# balloon_sensor_board.net
KiCad netlist of a schematic drawn in EAGLE
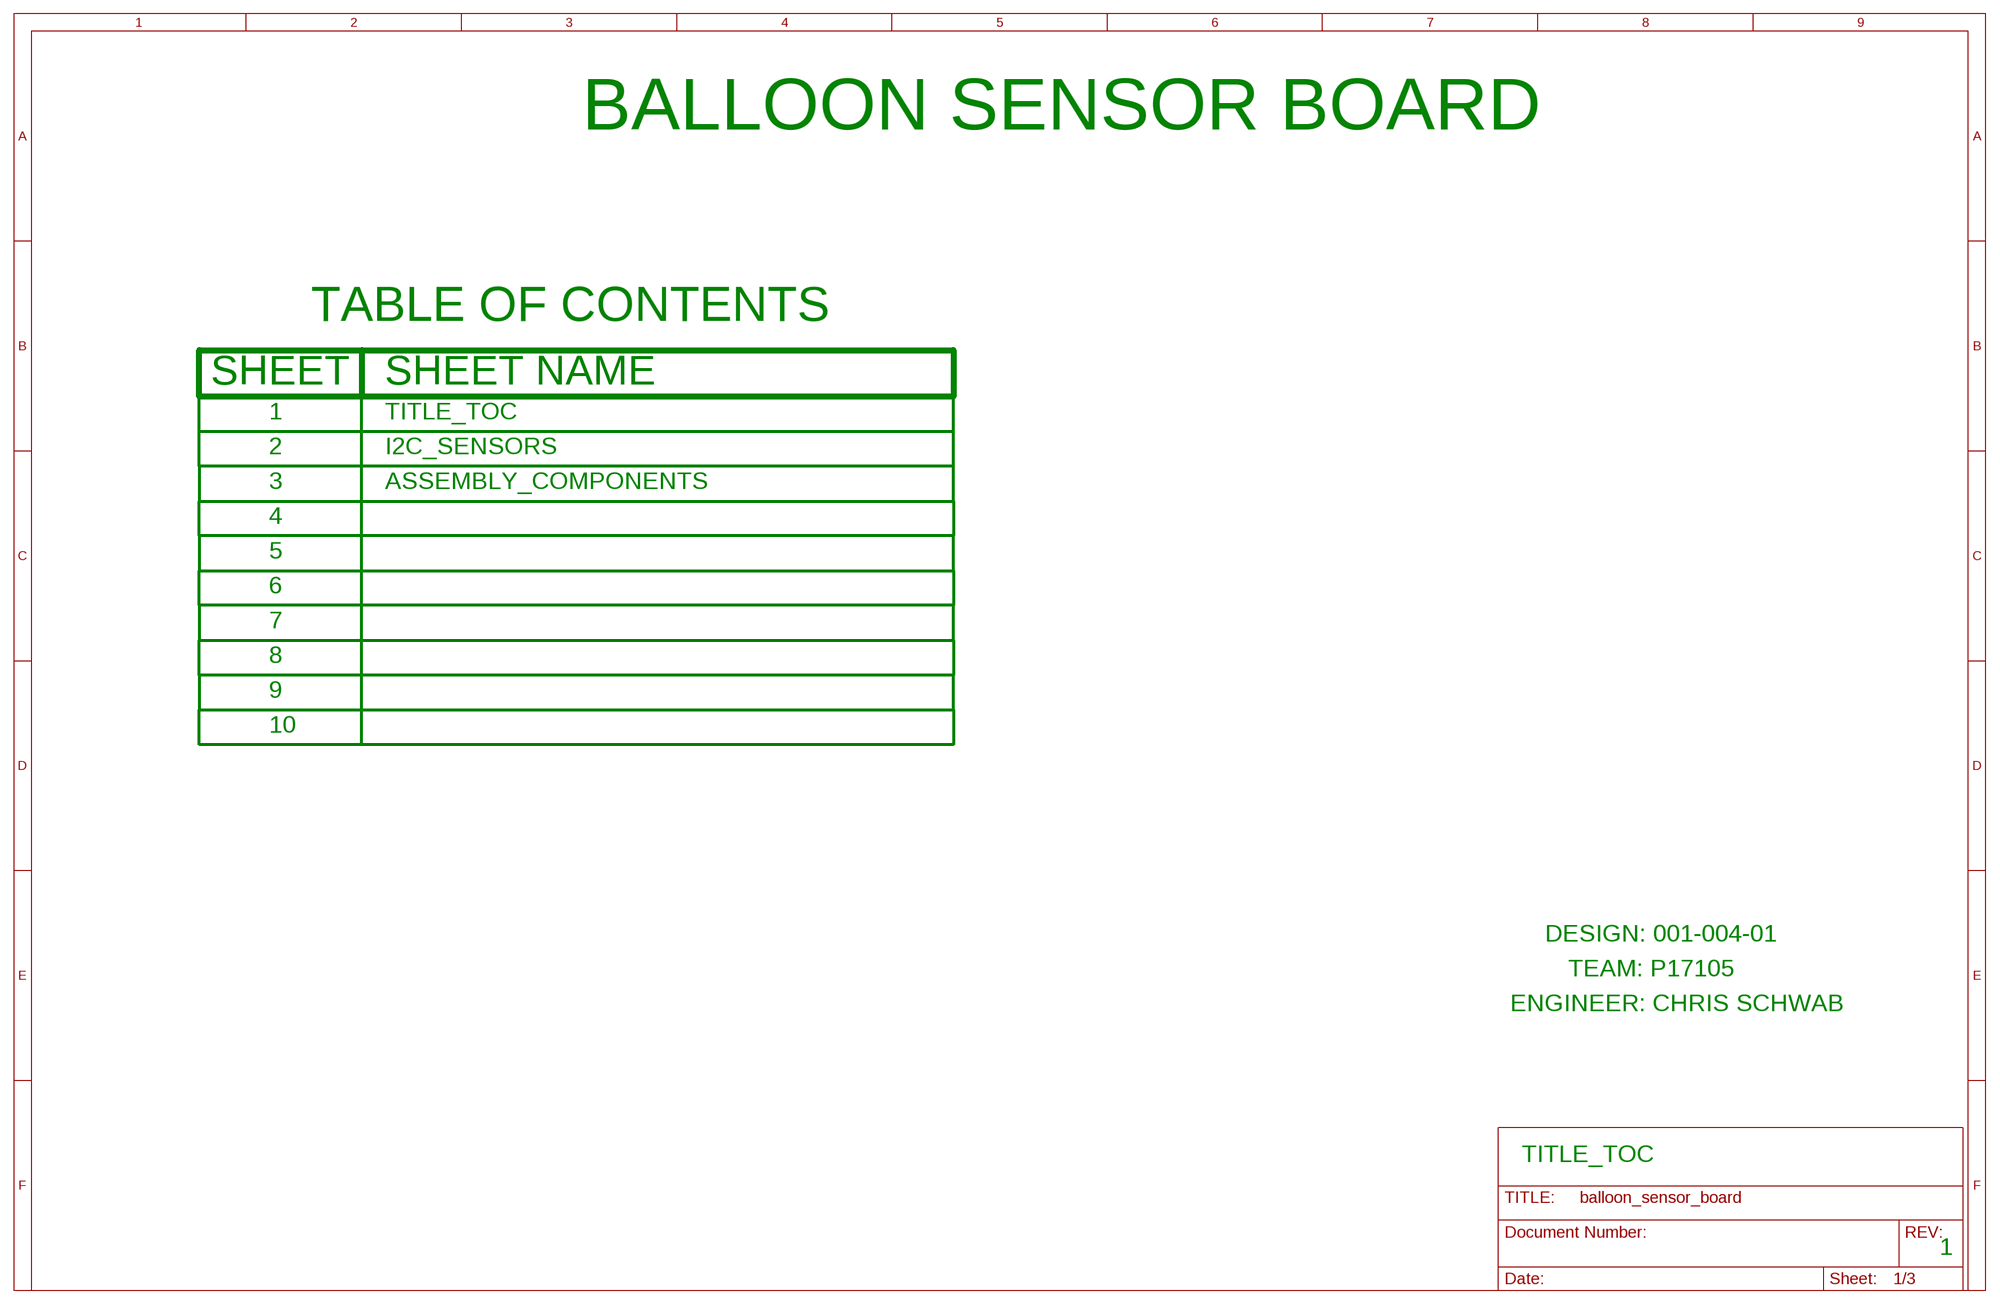
[diagram p0: schematic, sheet 1]
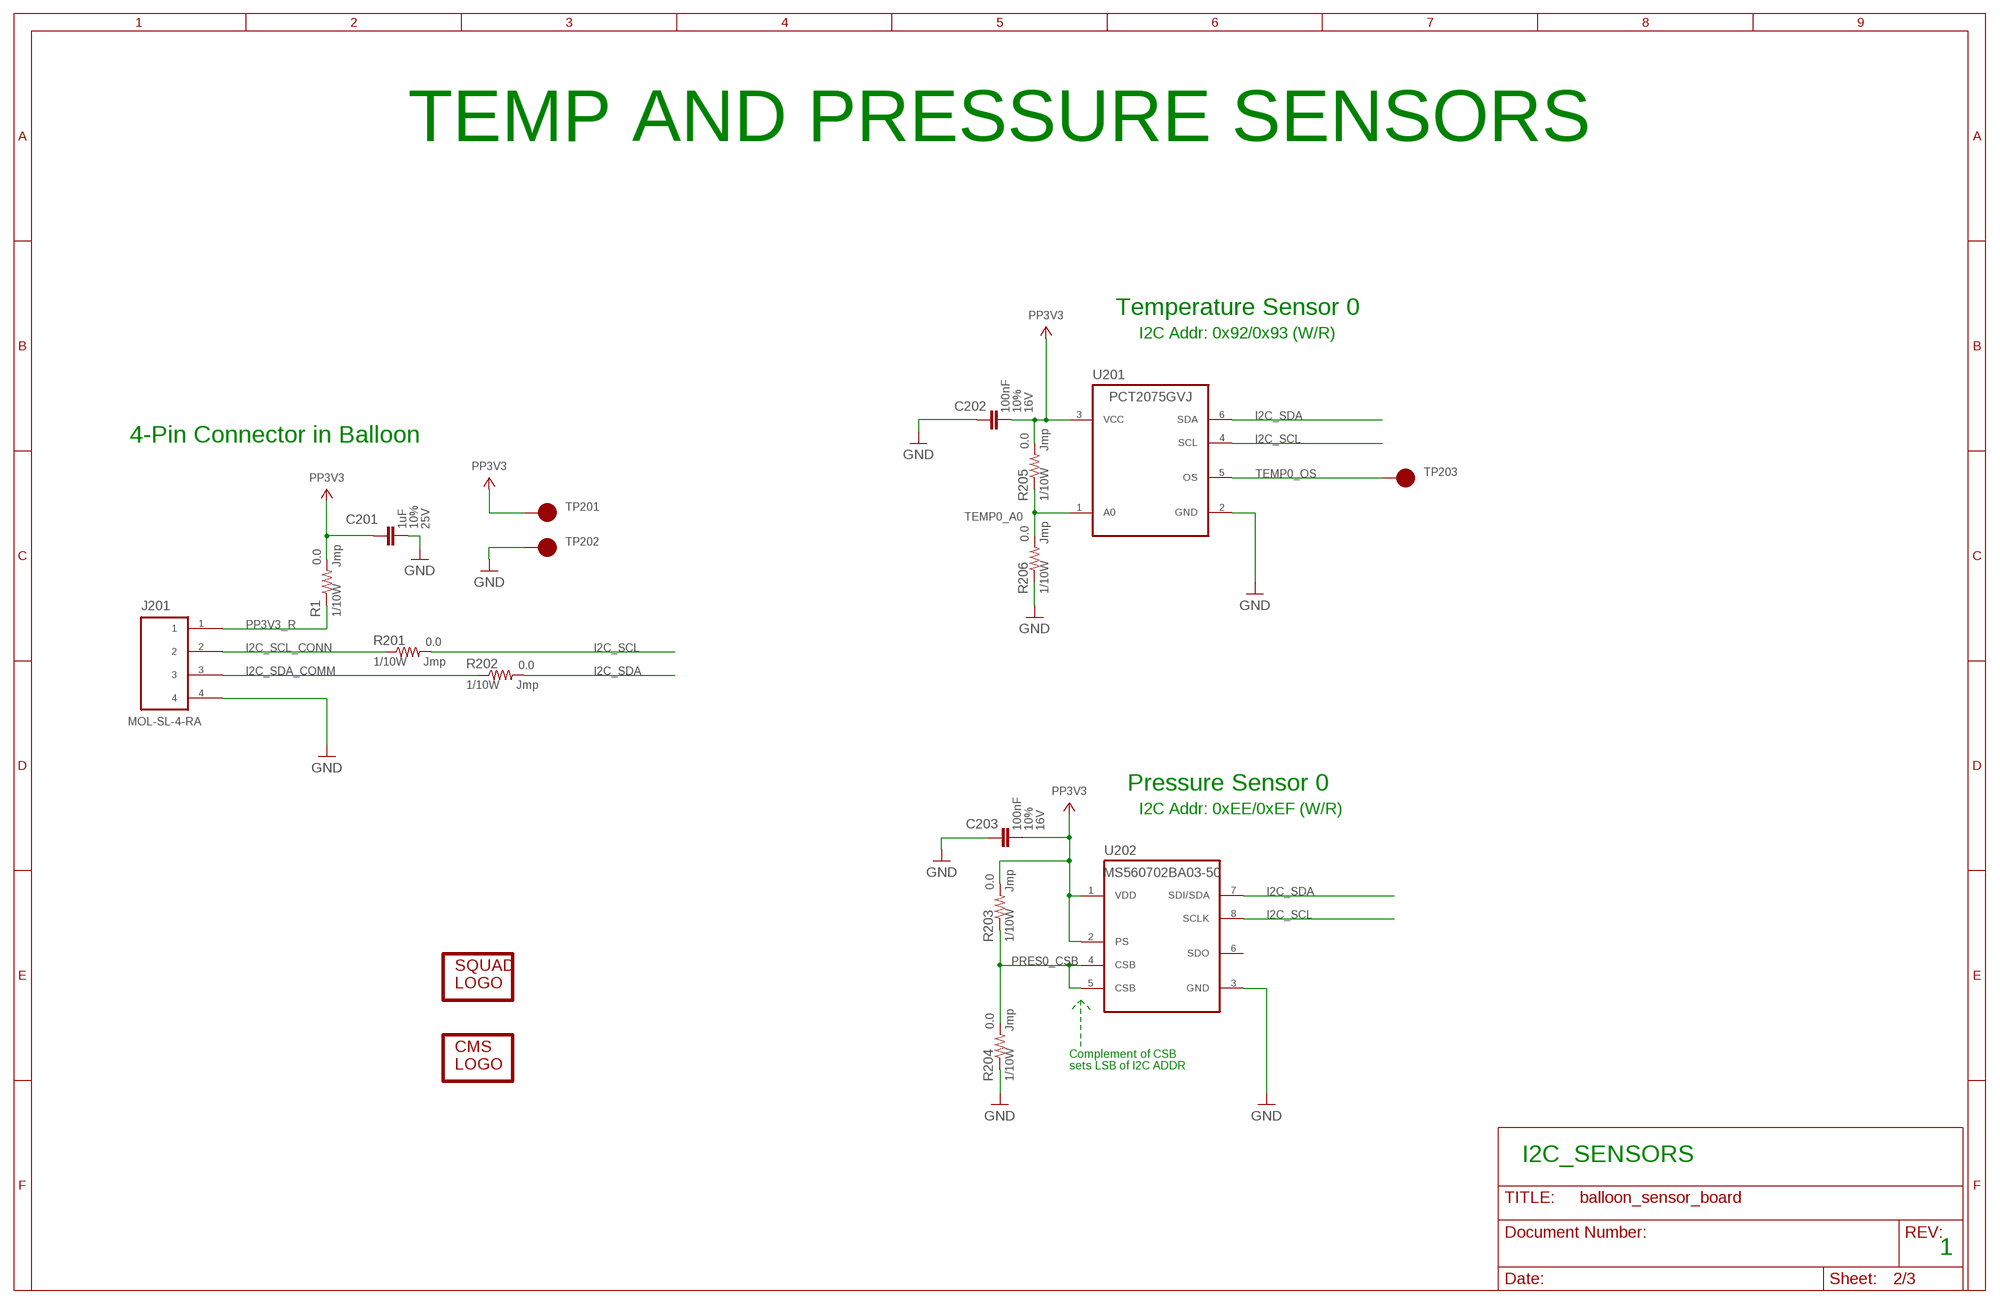
[diagram p1: schematic, sheet 2]
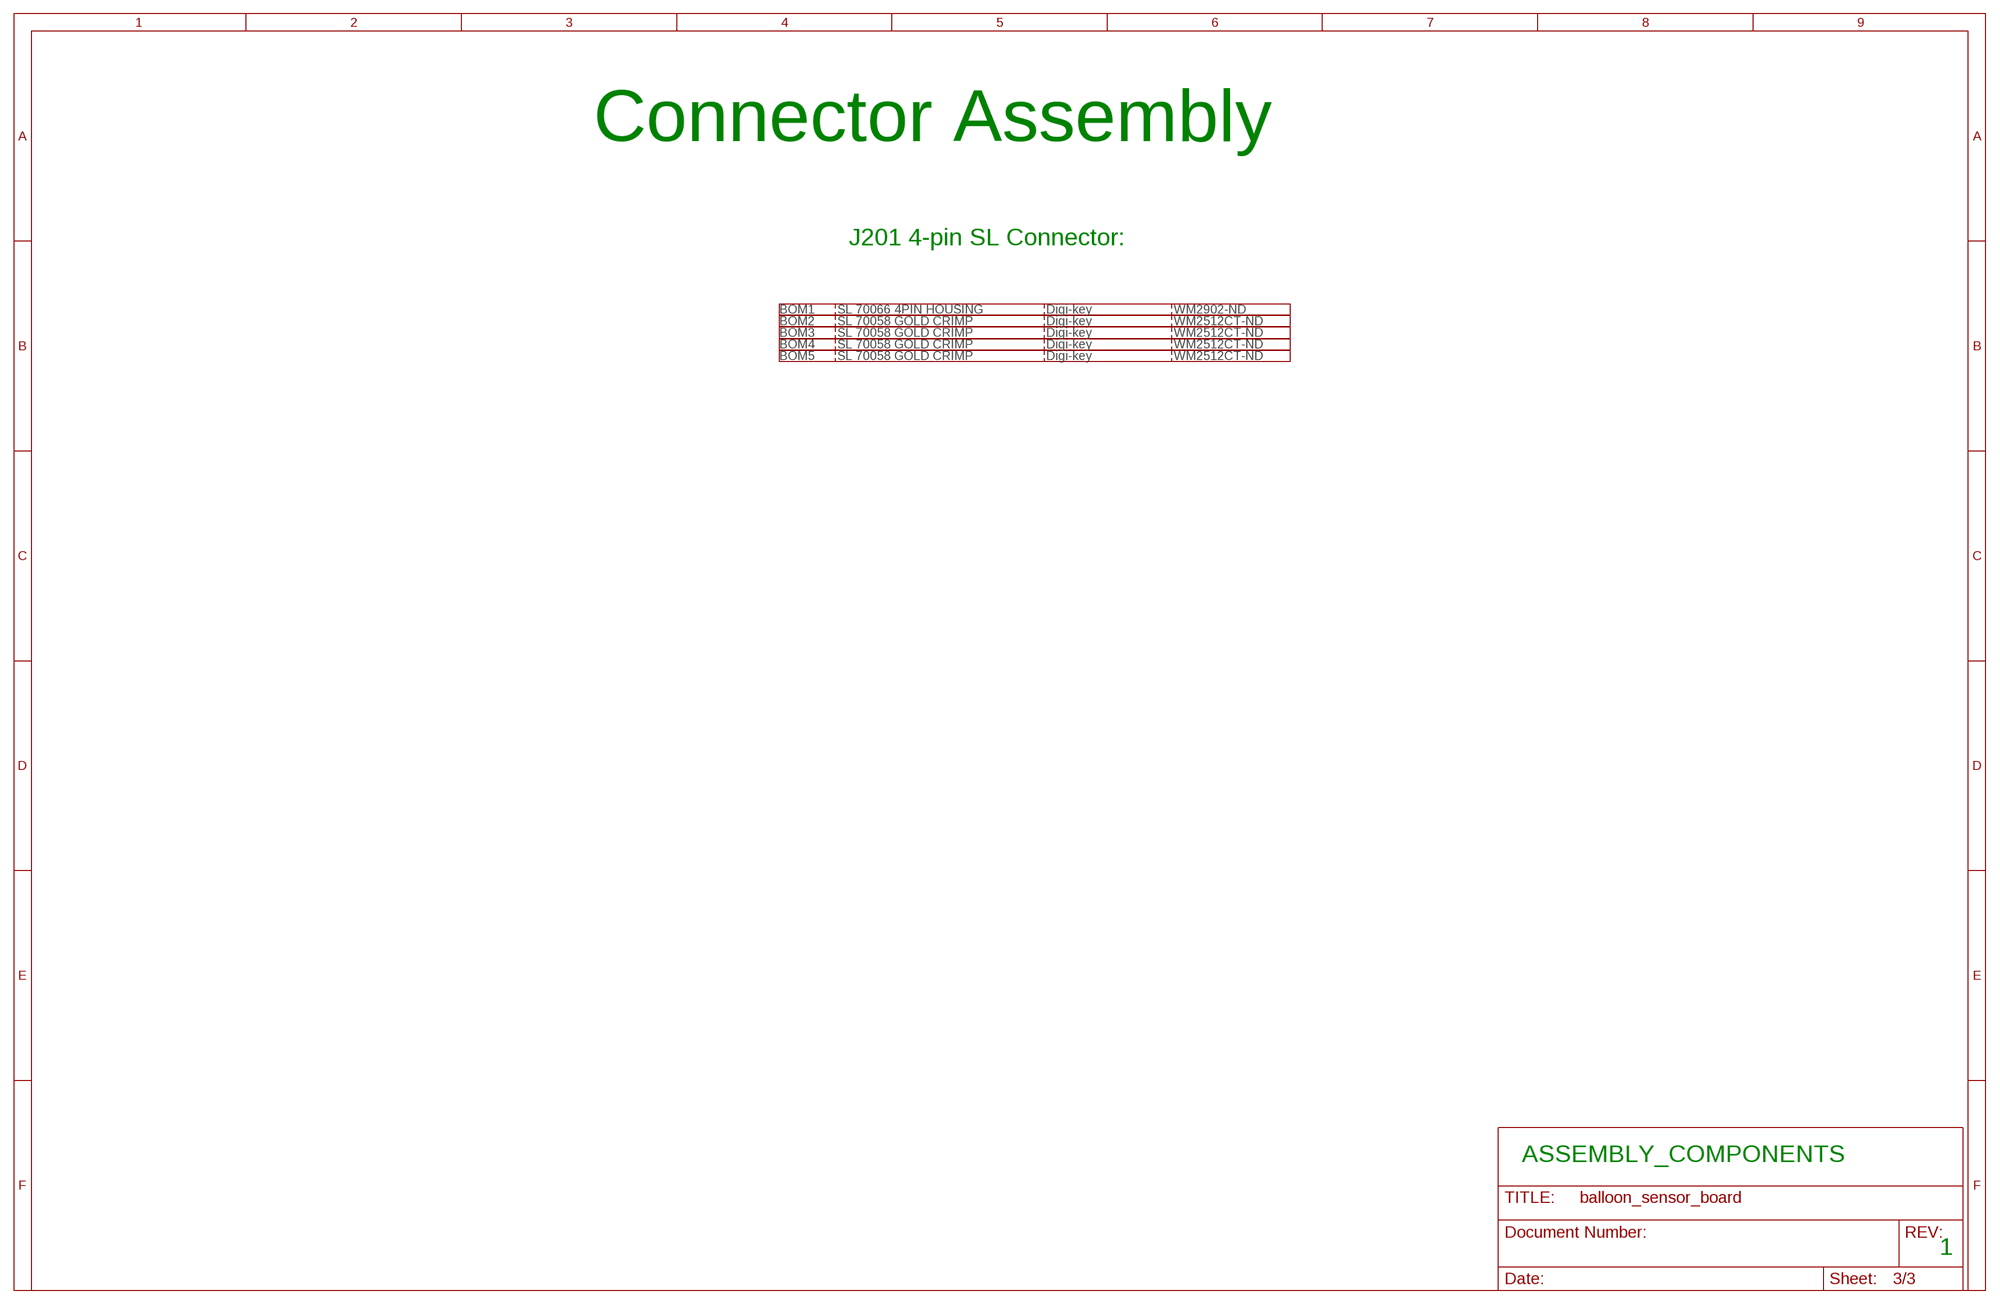
[diagram p2: schematic, sheet 3]

(export (version "E")
  (design (tool "Eeschema 10.0.6"))
  (components
    (comp (ref "BOM1")
      (value "SL 70066 4PIN HOUSING")
      (footprint "eagle-import:BLANK")
      (fields (field (name "MANUFACTURER") "Molex"))
      (libsource (lib "eagle-import") (part "BOM_LINE_ITEM_BLI4"))
    )
    (comp (ref "BOM2")
      (value "SL 70058 GOLD CRIMP")
      (footprint "eagle-import:BLANK")
      (fields (field (name "MANUFACTURER") "Molex"))
      (libsource (lib "eagle-import") (part "BOM_LINE_ITEM_BLI6"))
    )
    (comp (ref "BOM3")
      (value "SL 70058 GOLD CRIMP")
      (footprint "eagle-import:BLANK")
      (fields (field (name "MANUFACTURER") "Molex"))
      (libsource (lib "eagle-import") (part "BOM_LINE_ITEM_BLI6"))
    )
    (comp (ref "BOM4")
      (value "SL 70058 GOLD CRIMP")
      (footprint "eagle-import:BLANK")
      (fields (field (name "MANUFACTURER") "Molex"))
      (libsource (lib "eagle-import") (part "BOM_LINE_ITEM_BLI6"))
    )
    (comp (ref "BOM5")
      (value "SL 70058 GOLD CRIMP")
      (footprint "eagle-import:BLANK")
      (fields (field (name "MANUFACTURER") "Molex"))
      (libsource (lib "eagle-import") (part "BOM_LINE_ITEM_BLI6"))
    )
    (comp (ref "C201")
      (value "1uF")
      (footprint "eagle-import:C0603")
      (fields
        (field (name "MANUFACTURER") "Murata")
        (field (name "TOLERANCE") "10%")
        (field (name "VOLTAGE") "25V")
      )
      (libsource (lib "eagle-import") (part "CAP_0603_1UF0"))
    )
    (comp (ref "C202")
      (value "100nF")
      (footprint "eagle-import:C0603")
      (fields
        (field (name "MANUFACTURER") "Murata")
        (field (name "TOLERANCE") "10%")
        (field (name "VOLTAGE") "16V")
      )
      (libsource (lib "eagle-import") (part "CAP_0603_100NF0"))
    )
    (comp (ref "C203")
      (value "100nF")
      (footprint "eagle-import:C0603")
      (fields
        (field (name "MANUFACTURER") "Murata")
        (field (name "TOLERANCE") "10%")
        (field (name "VOLTAGE") "16V")
      )
      (libsource (lib "eagle-import") (part "CAP_0603_100NF0"))
    )
    (comp (ref "J201")
      (value "MOL-SL-4-RA")
      (footprint "eagle-import:MOLSL-4-RA")
      (fields (field (name "MANUFACTURER") "Molex"))
      (libsource (lib "eagle-import") (part "MOLSL_4PIN_RA_SL4RA"))
    )
    (comp (ref "LOGO201")
      (value "SQUAD_LOGO")
      (footprint "eagle-import:SQUAD_LOGO")
      (libsource (lib "eagle-import") (part "SQUAD_LOGO"))
    )
    (comp (ref "LOGO202")
      (value "CMS_LOGO")
      (footprint "eagle-import:CMS_LOGO")
      (libsource (lib "eagle-import") (part "CMS_LOGO"))
    )
    (comp (ref "R1")
      (value "0.0")
      (footprint "eagle-import:R0603")
      (fields
        (field (name "MANUFACTURER") "Panasonic")
        (field (name "POWER") "1/10W")
        (field (name "TOLERANCE") "Jmp")
      )
      (libsource (lib "eagle-import") (part "RES_0603_0R0"))
    )
    (comp (ref "R201")
      (value "0.0")
      (footprint "eagle-import:R0603")
      (fields
        (field (name "MANUFACTURER") "Panasonic")
        (field (name "POWER") "1/10W")
        (field (name "TOLERANCE") "Jmp")
      )
      (libsource (lib "eagle-import") (part "RES_0603_0R0"))
    )
    (comp (ref "R202")
      (value "0.0")
      (footprint "eagle-import:R0603")
      (fields
        (field (name "MANUFACTURER") "Panasonic")
        (field (name "POWER") "1/10W")
        (field (name "TOLERANCE") "Jmp")
      )
      (libsource (lib "eagle-import") (part "RES_0603_0R0"))
    )
    (comp (ref "R203")
      (value "0.0")
      (footprint "eagle-import:R0603")
      (fields
        (field (name "MANUFACTURER") "Panasonic")
        (field (name "POWER") "1/10W")
        (field (name "TOLERANCE") "Jmp")
      )
      (libsource (lib "eagle-import") (part "RES_0603_0R0"))
    )
    (comp (ref "R204")
      (value "0.0")
      (footprint "eagle-import:R0603")
      (fields
        (field (name "MANUFACTURER") "Panasonic")
        (field (name "POWER") "1/10W")
        (field (name "TOLERANCE") "Jmp")
      )
      (libsource (lib "eagle-import") (part "RES_0603_0R0"))
    )
    (comp (ref "R205")
      (value "0.0")
      (footprint "eagle-import:R0603")
      (fields
        (field (name "MANUFACTURER") "Panasonic")
        (field (name "POWER") "1/10W")
        (field (name "TOLERANCE") "Jmp")
      )
      (libsource (lib "eagle-import") (part "RES_0603_0R0"))
    )
    (comp (ref "R206")
      (value "0.0")
      (footprint "eagle-import:R0603")
      (fields
        (field (name "MANUFACTURER") "Panasonic")
        (field (name "POWER") "1/10W")
        (field (name "TOLERANCE") "Jmp")
      )
      (libsource (lib "eagle-import") (part "RES_0603_0R0"))
    )
    (comp (ref "TP201")
      (value "TEST_POINT_SMT_15R_SMD")
      (footprint "eagle-import:TP15R")
      (libsource (lib "eagle-import") (part "TEST_POINT_SMT_15R_SMD"))
    )
    (comp (ref "TP202")
      (value "TEST_POINT_SMT_15R_SMD")
      (footprint "eagle-import:TP15R")
      (libsource (lib "eagle-import") (part "TEST_POINT_SMT_15R_SMD"))
    )
    (comp (ref "TP203")
      (value "TEST_POINT_SMT_15R_SMD")
      (footprint "eagle-import:TP15R")
      (libsource (lib "eagle-import") (part "TEST_POINT_SMT_15R_SMD"))
    )
    (comp (ref "U201")
      (value "PCT2075GVJ")
      (footprint "eagle-import:TSOP95P080X055-6N")
      (fields (field (name "MANUFACTURER") "NXP"))
      (libsource (lib "eagle-import") (part "PCT2075GV_TSOP6"))
    )
    (comp (ref "U202")
      (value "MS560702BA03-50")
      (footprint "eagle-import:SMD125P110X060-8N")
      (fields (field (name "MANUFACTURER") "TE Connectivity"))
      (libsource (lib "eagle-import") (part "MS5607_8SMD-02BA03"))
    )
  )
  (nets
    (net (code "1") (name "GND") (class "Default")
      (node (ref "C201") (pin "2") (pinfunction "2_2") (pintype "passive"))
      (node (ref "C202") (pin "1") (pinfunction "1_1") (pintype "passive"))
      (node (ref "C203") (pin "1") (pinfunction "1_1") (pintype "passive"))
      (node (ref "J201") (pin "4") (pinfunction "4_4") (pintype "bidirectional"))
      (node (ref "R204") (pin "1") (pinfunction "1_1") (pintype "passive"))
      (node (ref "R206") (pin "1") (pinfunction "1_1") (pintype "passive"))
      (node (ref "TP202") (pin "TP") (pinfunction "TP_TP") (pintype "passive"))
      (node (ref "U201") (pin "2") (pinfunction "GND_2") (pintype "power_in"))
      (node (ref "U202") (pin "3") (pinfunction "GND_3") (pintype "power_in"))
    )
    (net (code "2") (name "I2C_SCL") (class "Default")
      (node (ref "R201") (pin "2") (pinfunction "2_2") (pintype "passive"))
      (node (ref "U201") (pin "4") (pinfunction "SCL_4") (pintype "input"))
      (node (ref "U202") (pin "8") (pinfunction "SCLK_8") (pintype "input"))
    )
    (net (code "3") (name "I2C_SCL_CONN") (class "Default")
      (node (ref "J201") (pin "2") (pinfunction "2_2") (pintype "bidirectional"))
      (node (ref "R201") (pin "1") (pinfunction "1_1") (pintype "passive"))
    )
    (net (code "4") (name "I2C_SDA") (class "Default")
      (node (ref "R202") (pin "2") (pinfunction "2_2") (pintype "passive"))
      (node (ref "U201") (pin "6") (pinfunction "SDA_6") (pintype "bidirectional"))
      (node (ref "U202") (pin "7") (pinfunction "SDI/SDA_7") (pintype "bidirectional"))
    )
    (net (code "5") (name "I2C_SDA_COMM") (class "Default")
      (node (ref "J201") (pin "3") (pinfunction "3_3") (pintype "bidirectional"))
      (node (ref "R202") (pin "1") (pinfunction "1_1") (pintype "passive"))
    )
    (net (code "6") (name "PP3V3") (class "Default")
      (node (ref "C201") (pin "1") (pinfunction "1_1") (pintype "passive"))
      (node (ref "C202") (pin "2") (pinfunction "2_2") (pintype "passive"))
      (node (ref "C203") (pin "2") (pinfunction "2_2") (pintype "passive"))
      (node (ref "R1") (pin "2") (pinfunction "2_2") (pintype "passive"))
      (node (ref "R203") (pin "2") (pinfunction "2_2") (pintype "passive"))
      (node (ref "R205") (pin "2") (pinfunction "2_2") (pintype "passive"))
      (node (ref "TP201") (pin "TP") (pinfunction "TP_TP") (pintype "passive"))
      (node (ref "U201") (pin "3") (pinfunction "VCC_3") (pintype "power_in"))
      (node (ref "U202") (pin "1") (pinfunction "VDD_1") (pintype "power_in"))
      (node (ref "U202") (pin "2") (pinfunction "PS_2") (pintype "input"))
    )
    (net (code "7") (name "PP3V3_R") (class "Default")
      (node (ref "J201") (pin "1") (pinfunction "1_1") (pintype "bidirectional"))
      (node (ref "R1") (pin "1") (pinfunction "1_1") (pintype "passive"))
    )
    (net (code "8") (name "PRES0_CSB") (class "Default")
      (node (ref "R203") (pin "1") (pinfunction "1_1") (pintype "passive"))
      (node (ref "R204") (pin "2") (pinfunction "2_2") (pintype "passive"))
      (node (ref "U202") (pin "4") (pinfunction "CSB_4") (pintype "input"))
      (node (ref "U202") (pin "5") (pinfunction "CSB_5") (pintype "output"))
    )
    (net (code "9") (name "TEMP0_A0") (class "Default")
      (node (ref "R205") (pin "1") (pinfunction "1_1") (pintype "passive"))
      (node (ref "R206") (pin "2") (pinfunction "2_2") (pintype "passive"))
      (node (ref "U201") (pin "1") (pinfunction "A0_1") (pintype "input"))
    )
    (net (code "10") (name "TEMP0_OS") (class "Default")
      (node (ref "TP203") (pin "TP") (pinfunction "TP_TP") (pintype "passive"))
      (node (ref "U201") (pin "5") (pinfunction "OS_5") (pintype "output"))
    )
    (net (code "11") (name "unconnected-(U202-SDO-Pad6)") (class "Default")
      (node (ref "U202") (pin "6") (pinfunction "SDO_6") (pintype "output"))
    )
  )
)
